# Protocol-Analyzer.net
KiCad netlist of a schematic drawn in Altium Designer
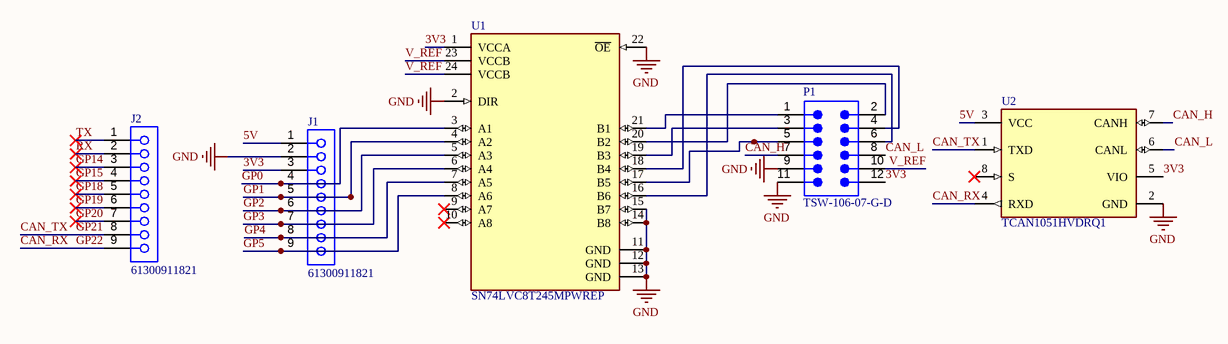
[diagram p0: Protocol-Analyzer.SchDoc]

(export (version "E")
  (design (tool "Eeschema 10.0.6"))
  (components
    (comp (ref "J1")
      (value "61300911821")
      (footprint "61300911821")
      (description "THT Vertical Socket Header WR-PHD, Pitch 2.54 mm, Single Row, 9 pins")
      (libsource (lib "Altium Content Vault") (part "Header_Female_1R_09P"))
    )
    (comp (ref "J2")
      (value "61300911821")
      (footprint "61300911821")
      (description "THT Vertical Socket Header WR-PHD, Pitch 2.54 mm, Single Row, 9 pins")
      (libsource (lib "Altium Content Vault") (part "Header_Female_1R_09P"))
    )
    (comp (ref "P1")
      (value "TSW-106-07-G-D")
      (footprint "SMTC-TSW-106-07-X-D")
      (description "0.025\" SQ Post Header, Through-hole, Vertical, -55 to 125 degC, 2.54 mm Pitch, 12-Pin, Male, RoHS")
      (fields (field (name "MANUFACTURER") "Samtec"))
      (libsource (lib "Altium Content Vault") (part "SMTC-TSW-106-07-X-D"))
    )
    (comp (ref "U1")
      (value "SN74LVC8T245MPWREP")
      (footprint "FP-PW0024A-IPC_A")
      (description "IC TRNSLTR BIDIRECTIONAL 24TSSOP")
      (libsource (lib "Altium Content Vault") (part "76af71cc6744c3f4b71f5f94c028a33"))
    )
    (comp (ref "U2")
      (value "TCAN1051HVDRQ1")
      (footprint "FP-D0008B-IPC_C")
      (description "IC TRANSCEIVER HALF 1/1 8SOIC")
      (libsource (lib "Altium Content Vault") (part "16ab02568aafc22d978fbc4c18e6710"))
    )
  )
  (nets
    (net (code "1") (name "/3V3") (class "Default")
      (node (ref "J1") (pin "3") (pinfunction "3_3") (pintype "passive"))
      (node (ref "P1") (pin "12") (pinfunction "12_12") (pintype "passive"))
      (node (ref "U1") (pin "1") (pinfunction "VCCA_1") (pintype "power_in"))
      (node (ref "U2") (pin "5") (pinfunction "VIO_5") (pintype "power_in"))
    )
    (net (code "2") (name "/5V") (class "Default")
      (node (ref "J1") (pin "1") (pinfunction "1_1") (pintype "passive"))
      (node (ref "U2") (pin "3") (pinfunction "VCC_3") (pintype "power_in"))
    )
    (net (code "3") (name "/CAN_H") (class "Default")
      (node (ref "P1") (pin "7") (pinfunction "7_7") (pintype "passive"))
      (node (ref "U2") (pin "7") (pinfunction "CANH_7") (pintype "bidirectional"))
    )
    (net (code "4") (name "/CAN_L") (class "Default")
      (node (ref "P1") (pin "8") (pinfunction "8_8") (pintype "passive"))
      (node (ref "U2") (pin "6") (pinfunction "CANL_6") (pintype "bidirectional"))
    )
    (net (code "5") (name "/CAN_RX") (class "Default")
      (node (ref "J2") (pin "9") (pinfunction "9_9") (pintype "passive"))
      (node (ref "U2") (pin "4") (pinfunction "RXD_4") (pintype "output"))
    )
    (net (code "6") (name "/CAN_TX") (class "Default")
      (node (ref "J2") (pin "8") (pinfunction "8_8") (pintype "passive"))
      (node (ref "U2") (pin "1") (pinfunction "TXD_1") (pintype "input"))
    )
    (net (code "7") (name "/GP0") (class "Default")
      (node (ref "J1") (pin "4") (pinfunction "4_4") (pintype "passive"))
      (node (ref "U1") (pin "3") (pinfunction "A1_3") (pintype "bidirectional"))
    )
    (net (code "8") (name "/GP1") (class "Default")
      (node (ref "J1") (pin "5") (pinfunction "5_5") (pintype "passive"))
      (node (ref "U1") (pin "4") (pinfunction "A2_4") (pintype "bidirectional"))
    )
    (net (code "9") (name "/GP2") (class "Default")
      (node (ref "J1") (pin "6") (pinfunction "6_6") (pintype "passive"))
      (node (ref "U1") (pin "5") (pinfunction "A3_5") (pintype "bidirectional"))
    )
    (net (code "10") (name "/GP3") (class "Default")
      (node (ref "J1") (pin "7") (pinfunction "7_7") (pintype "passive"))
      (node (ref "U1") (pin "6") (pinfunction "A4_6") (pintype "bidirectional"))
    )
    (net (code "11") (name "/GP4") (class "Default")
      (node (ref "J1") (pin "8") (pinfunction "8_8") (pintype "passive"))
      (node (ref "U1") (pin "7") (pinfunction "A5_7") (pintype "bidirectional"))
    )
    (net (code "12") (name "/GP5") (class "Default")
      (node (ref "J1") (pin "9") (pinfunction "9_9") (pintype "passive"))
      (node (ref "U1") (pin "8") (pinfunction "A6_8") (pintype "bidirectional"))
    )
    (net (code "13") (name "/GP14") (class "Default")
      (node (ref "J2") (pin "3") (pinfunction "3_3") (pintype "passive+no_connect"))
    )
    (net (code "14") (name "/GP15") (class "Default")
      (node (ref "J2") (pin "4") (pinfunction "4_4") (pintype "passive+no_connect"))
    )
    (net (code "15") (name "/GP18") (class "Default")
      (node (ref "J2") (pin "5") (pinfunction "5_5") (pintype "passive+no_connect"))
    )
    (net (code "16") (name "/GP19") (class "Default")
      (node (ref "J2") (pin "6") (pinfunction "6_6") (pintype "passive+no_connect"))
    )
    (net (code "17") (name "/GP20") (class "Default")
      (node (ref "J2") (pin "7") (pinfunction "7_7") (pintype "passive+no_connect"))
    )
    (net (code "18") (name "/RX") (class "Default")
      (node (ref "J2") (pin "2") (pinfunction "2_2") (pintype "passive+no_connect"))
    )
    (net (code "19") (name "/TX") (class "Default")
      (node (ref "J2") (pin "1") (pinfunction "1_1") (pintype "passive+no_connect"))
    )
    (net (code "20") (name "/V_REF") (class "Default")
      (node (ref "P1") (pin "10") (pinfunction "10_10") (pintype "passive"))
      (node (ref "U1") (pin "23") (pinfunction "VCCB_23") (pintype "power_in"))
      (node (ref "U1") (pin "24") (pinfunction "VCCB_24") (pintype "power_in"))
    )
    (net (code "21") (name "GND") (class "Default")
      (node (ref "J1") (pin "2") (pinfunction "2_2") (pintype "passive"))
      (node (ref "P1") (pin "11") (pinfunction "11_11") (pintype "passive"))
      (node (ref "P1") (pin "9") (pinfunction "9_9") (pintype "passive"))
      (node (ref "U1") (pin "11") (pinfunction "GND_11") (pintype "power_in"))
      (node (ref "U1") (pin "12") (pinfunction "GND_12") (pintype "power_in"))
      (node (ref "U1") (pin "13") (pinfunction "GND_13") (pintype "power_in"))
      (node (ref "U1") (pin "14") (pinfunction "B8_14") (pintype "bidirectional"))
      (node (ref "U1") (pin "15") (pinfunction "B7_15") (pintype "bidirectional"))
      (node (ref "U1") (pin "2") (pinfunction "DIR_2") (pintype "input"))
      (node (ref "U1") (pin "22") (pinfunction "~{OE}_22") (pintype "input"))
      (node (ref "U2") (pin "2") (pinfunction "GND_2") (pintype "power_in"))
    )
    (net (code "22") (name "Net-(U1-B1)") (class "Default")
      (node (ref "P1") (pin "1") (pinfunction "1_1") (pintype "passive"))
      (node (ref "U1") (pin "21") (pinfunction "B1_21") (pintype "bidirectional"))
    )
    (net (code "23") (name "Net-(U1-B2)") (class "Default")
      (node (ref "P1") (pin "2") (pinfunction "2_2") (pintype "passive"))
      (node (ref "U1") (pin "20") (pinfunction "B2_20") (pintype "bidirectional"))
    )
    (net (code "24") (name "Net-(U1-B3)") (class "Default")
      (node (ref "P1") (pin "3") (pinfunction "3_3") (pintype "passive"))
      (node (ref "U1") (pin "19") (pinfunction "B3_19") (pintype "bidirectional"))
    )
    (net (code "25") (name "Net-(U1-B4)") (class "Default")
      (node (ref "P1") (pin "4") (pinfunction "4_4") (pintype "passive"))
      (node (ref "U1") (pin "18") (pinfunction "B4_18") (pintype "bidirectional"))
    )
    (net (code "26") (name "Net-(U1-B5)") (class "Default")
      (node (ref "P1") (pin "5") (pinfunction "5_5") (pintype "passive"))
      (node (ref "U1") (pin "17") (pinfunction "B5_17") (pintype "bidirectional"))
    )
    (net (code "27") (name "Net-(U1-B6)") (class "Default")
      (node (ref "P1") (pin "6") (pinfunction "6_6") (pintype "passive"))
      (node (ref "U1") (pin "16") (pinfunction "B6_16") (pintype "bidirectional"))
    )
    (net (code "28") (name "unconnected-(U1-A7-Pad9)") (class "Default")
      (node (ref "U1") (pin "9") (pinfunction "A7_9") (pintype "bidirectional+no_connect"))
    )
    (net (code "29") (name "unconnected-(U1-A8-Pad10)") (class "Default")
      (node (ref "U1") (pin "10") (pinfunction "A8_10") (pintype "bidirectional+no_connect"))
    )
    (net (code "30") (name "unconnected-(U2-S-Pad8)") (class "Default")
      (node (ref "U2") (pin "8") (pinfunction "S_8") (pintype "input+no_connect"))
    )
  )
)
